# MPPT.net
KiCad netlist of a schematic drawn in Altium Designer
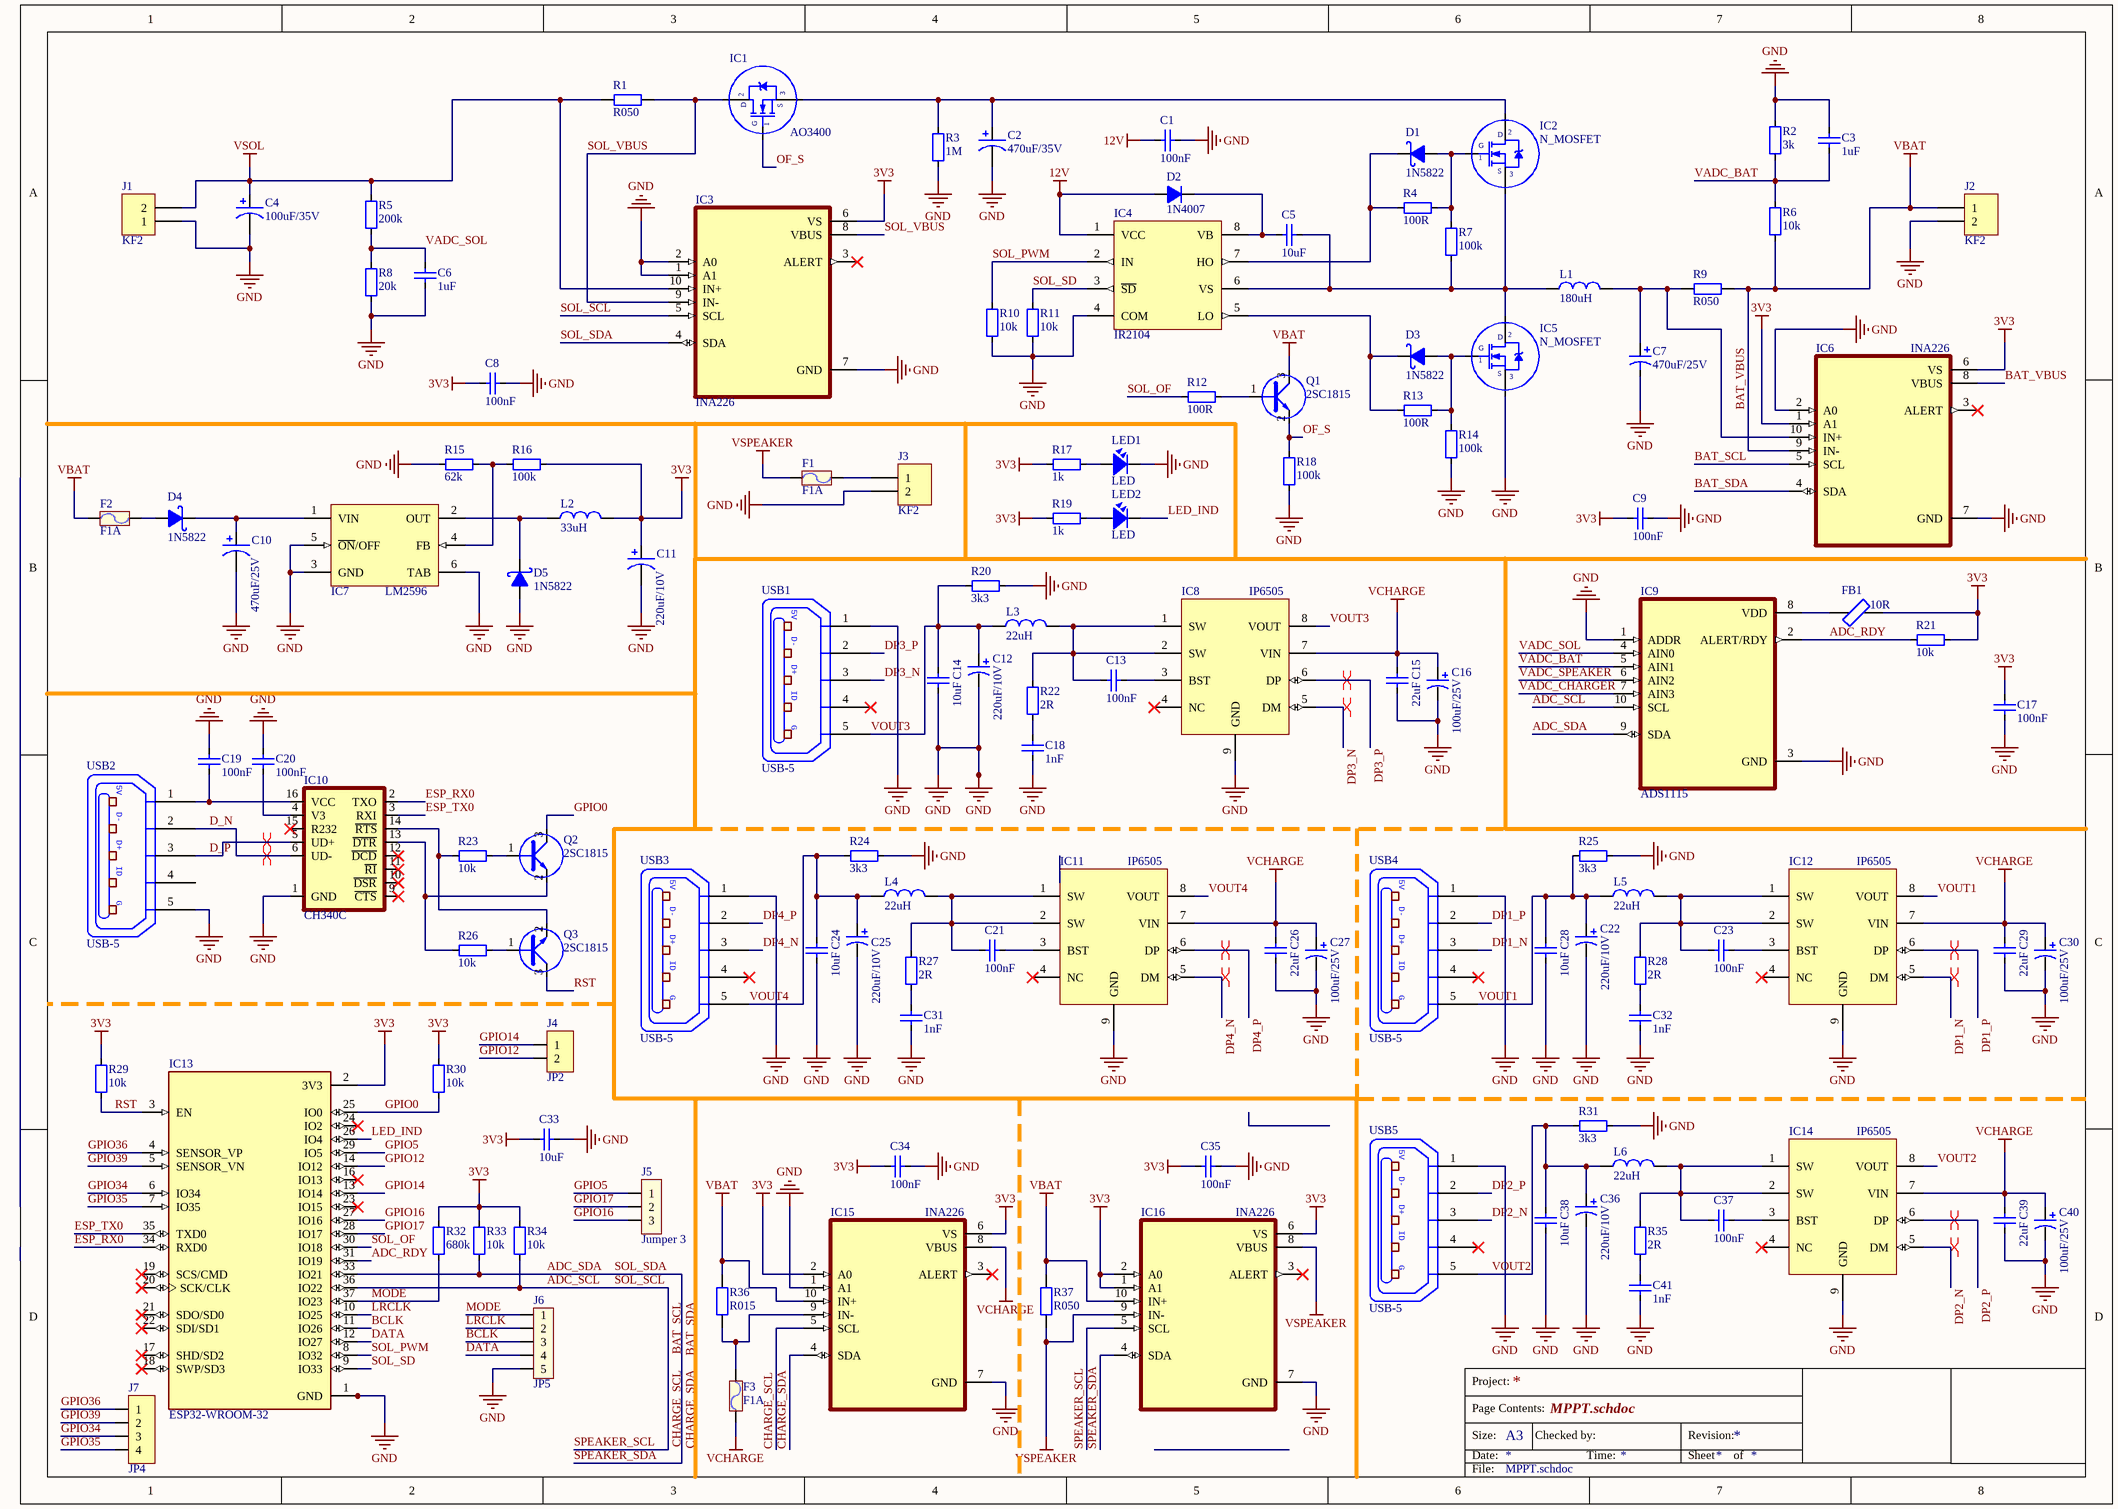
[diagram p0: MPPT.schdoc]

(export (version "E")
  (design (tool "Eeschema 10.0.6"))
  (components
    (comp (ref "C1")
      (value "100nF")
      (footprint "CAP_0805")
      (description "Capacitor")
      (fields (field (name "PUBLISHER") "Altium Limited"))
      (libsource (lib "My Library") (part "CapSMD"))
    )
    (comp (ref "C2")
      (value "470uF/35V")
      (footprint "CAP_H17_D10")
      (description "Polarized Capacitor (Axial)")
      (fields (field (name "PUBLISHER") "Altium Limited"))
      (libsource (lib "My Library") (part "Cap Pol"))
    )
    (comp (ref "C3")
      (value "1uF")
      (footprint "CAP_0805")
      (description "Capacitor")
      (fields (field (name "PUBLISHER") "Altium Limited"))
      (libsource (lib "My Library") (part "CapSMD"))
    )
    (comp (ref "C4")
      (value "100uF/35V")
      (footprint "CAP_H12_D06")
      (description "Polarized Capacitor (Axial)")
      (fields (field (name "PUBLISHER") "Altium Limited"))
      (libsource (lib "My Library") (part "Cap Pol"))
    )
    (comp (ref "C5")
      (value "10uF")
      (footprint "CAP_0805")
      (description "Capacitor")
      (fields (field (name "PUBLISHER") "Altium Limited"))
      (libsource (lib "My Library") (part "CapSMD"))
    )
    (comp (ref "C6")
      (value "1uF")
      (footprint "CAP_0805")
      (description "Capacitor")
      (fields (field (name "PUBLISHER") "Altium Limited"))
      (libsource (lib "My Library") (part "CapSMD"))
    )
    (comp (ref "C7")
      (value "470uF/25V")
      (footprint "C8mm")
      (description "Polarized Capacitor (Axial)")
      (fields (field (name "PUBLISHER") "Altium Limited"))
      (libsource (lib "") (part "Cap Pol_1"))
    )
    (comp (ref "C8")
      (value "100nF")
      (footprint "CAP_0805")
      (description "Capacitor")
      (fields (field (name "PUBLISHER") "Altium Limited"))
      (libsource (lib "My Library") (part "CapSMD"))
    )
    (comp (ref "C9")
      (value "100nF")
      (footprint "CAP_0805")
      (description "Capacitor")
      (fields (field (name "PUBLISHER") "Altium Limited"))
      (libsource (lib "My Library") (part "CapSMD"))
    )
    (comp (ref "C10")
      (value "470uF/25V")
      (footprint "C8mm")
      (description "Polarized Capacitor (Axial)")
      (fields (field (name "PUBLISHER") "Altium Limited"))
      (libsource (lib "My Library") (part "Cap Pol"))
    )
    (comp (ref "C11")
      (value "220uF/10V")
      (footprint "C5mm")
      (description "Polarized Capacitor (Axial)")
      (fields (field (name "PUBLISHER") "Altium Limited"))
      (libsource (lib "My Library") (part "Cap Pol"))
    )
    (comp (ref "C12")
      (value "220uF/10V")
      (footprint "CAP_3216")
      (description "Polazied Tantalum Capacitor")
      (libsource (lib "My Library") (part "CAP_TAN_SMD"))
    )
    (comp (ref "C13")
      (value "100nF")
      (footprint "CAP_0805")
      (description "Capacitor")
      (fields (field (name "PUBLISHER") "Altium Limited"))
      (libsource (lib "My Library") (part "CapSMD"))
    )
    (comp (ref "C14")
      (value "10uF")
      (footprint "CAP_0805")
      (description "Capacitor")
      (fields (field (name "PUBLISHER") "Altium Limited"))
      (libsource (lib "My Library") (part "CapSMD"))
    )
    (comp (ref "C15")
      (value "22uF")
      (footprint "CAP_0805")
      (description "Capacitor")
      (fields (field (name "PUBLISHER") "Altium Limited"))
      (libsource (lib "My Library") (part "CapSMD"))
    )
    (comp (ref "C16")
      (value "100uF/25V")
      (footprint "CAP_3528")
      (description "Polazied Tantalum Capacitor")
      (libsource (lib "My Library") (part "CAP_TAN_SMD"))
    )
    (comp (ref "C17")
      (value "100nF")
      (footprint "CAP_0805")
      (description "Capacitor")
      (fields (field (name "PUBLISHER") "Altium Limited"))
      (libsource (lib "My Library") (part "CapSMD"))
    )
    (comp (ref "C18")
      (value "1nF")
      (footprint "CAP_0805")
      (description "Capacitor")
      (fields (field (name "PUBLISHER") "Altium Limited"))
      (libsource (lib "My Library") (part "CapSMD"))
    )
    (comp (ref "C19")
      (value "100nF")
      (footprint "CAP_0805")
      (description "Capacitor")
      (fields (field (name "PUBLISHER") "Altium Limited"))
      (libsource (lib "My Library") (part "CapSMD"))
    )
    (comp (ref "C20")
      (value "100nF")
      (footprint "CAP_0805")
      (description "Capacitor")
      (fields (field (name "PUBLISHER") "Altium Limited"))
      (libsource (lib "My Library") (part "CapSMD"))
    )
    (comp (ref "C21")
      (value "100nF")
      (footprint "CAP_0805")
      (description "Capacitor")
      (fields (field (name "PUBLISHER") "Altium Limited"))
      (libsource (lib "My Library") (part "CapSMD"))
    )
    (comp (ref "C22")
      (value "220uF/10V")
      (footprint "CAP_3216")
      (description "Polazied Tantalum Capacitor")
      (libsource (lib "My Library") (part "CAP_TAN_SMD"))
    )
    (comp (ref "C23")
      (value "100nF")
      (footprint "CAP_0805")
      (description "Capacitor")
      (fields (field (name "PUBLISHER") "Altium Limited"))
      (libsource (lib "My Library") (part "CapSMD"))
    )
    (comp (ref "C24")
      (value "10uF")
      (footprint "CAP_0805")
      (description "Capacitor")
      (fields (field (name "PUBLISHER") "Altium Limited"))
      (libsource (lib "My Library") (part "CapSMD"))
    )
    (comp (ref "C25")
      (value "220uF/10V")
      (footprint "CAP_3216")
      (description "Polazied Tantalum Capacitor")
      (libsource (lib "My Library") (part "CAP_TAN_SMD"))
    )
    (comp (ref "C26")
      (value "22uF")
      (footprint "CAP_0805")
      (description "Capacitor")
      (fields (field (name "PUBLISHER") "Altium Limited"))
      (libsource (lib "My Library") (part "CapSMD"))
    )
    (comp (ref "C27")
      (value "100uF/25V")
      (footprint "CAP_3528")
      (description "Polazied Tantalum Capacitor")
      (libsource (lib "My Library") (part "CAP_TAN_SMD"))
    )
    (comp (ref "C28")
      (value "10uF")
      (footprint "CAP_0805")
      (description "Capacitor")
      (fields (field (name "PUBLISHER") "Altium Limited"))
      (libsource (lib "My Library") (part "CapSMD"))
    )
    (comp (ref "C29")
      (value "22uF")
      (footprint "CAP_0805")
      (description "Capacitor")
      (fields (field (name "PUBLISHER") "Altium Limited"))
      (libsource (lib "My Library") (part "CapSMD"))
    )
    (comp (ref "C30")
      (value "100uF/25V")
      (footprint "CAP_3528")
      (description "Polazied Tantalum Capacitor")
      (libsource (lib "My Library") (part "CAP_TAN_SMD"))
    )
    (comp (ref "C31")
      (value "1nF")
      (footprint "CAP_0805")
      (description "Capacitor")
      (fields (field (name "PUBLISHER") "Altium Limited"))
      (libsource (lib "My Library") (part "CapSMD"))
    )
    (comp (ref "C32")
      (value "1nF")
      (footprint "CAP_0805")
      (description "Capacitor")
      (fields (field (name "PUBLISHER") "Altium Limited"))
      (libsource (lib "My Library") (part "CapSMD"))
    )
    (comp (ref "C33")
      (value "10uF")
      (footprint "CAP_0805")
      (description "Capacitor")
      (fields (field (name "PUBLISHER") "Altium Limited"))
      (libsource (lib "My Library") (part "CapSMD"))
    )
    (comp (ref "C34")
      (value "100nF")
      (footprint "CAP_0805")
      (description "Capacitor")
      (fields (field (name "PUBLISHER") "Altium Limited"))
      (libsource (lib "My Library") (part "CapSMD"))
    )
    (comp (ref "C35")
      (value "100nF")
      (footprint "CAP_0805")
      (description "Capacitor")
      (fields (field (name "PUBLISHER") "Altium Limited"))
      (libsource (lib "My Library") (part "CapSMD"))
    )
    (comp (ref "C36")
      (value "220uF/10V")
      (footprint "CAP_3216")
      (description "Polazied Tantalum Capacitor")
      (libsource (lib "My Library") (part "CAP_TAN_SMD"))
    )
    (comp (ref "C37")
      (value "100nF")
      (footprint "CAP_0805")
      (description "Capacitor")
      (fields (field (name "PUBLISHER") "Altium Limited"))
      (libsource (lib "My Library") (part "CapSMD"))
    )
    (comp (ref "C38")
      (value "10uF")
      (footprint "CAP_0805")
      (description "Capacitor")
      (fields (field (name "PUBLISHER") "Altium Limited"))
      (libsource (lib "My Library") (part "CapSMD"))
    )
    (comp (ref "C39")
      (value "22uF")
      (footprint "CAP_0805")
      (description "Capacitor")
      (fields (field (name "PUBLISHER") "Altium Limited"))
      (libsource (lib "My Library") (part "CapSMD"))
    )
    (comp (ref "C40")
      (value "100uF/25V")
      (footprint "CAP_3528")
      (description "Polazied Tantalum Capacitor")
      (libsource (lib "My Library") (part "CAP_TAN_SMD"))
    )
    (comp (ref "C41")
      (value "1nF")
      (footprint "CAP_0805")
      (description "Capacitor")
      (fields (field (name "PUBLISHER") "Altium Limited"))
      (libsource (lib "My Library") (part "CapSMD"))
    )
    (comp (ref "D1")
      (value "1N5822")
      (footprint "DIO-214AC(SMA)")
      (description "Schottky Rectifiers")
      (libsource (lib "My Library") (part "1N5822"))
    )
    (comp (ref "D2")
      (value "1N4007")
      (footprint "D1A")
      (description "Diode 1A")
      (libsource (lib "My Library") (part "D1A"))
    )
    (comp (ref "D3")
      (value "1N5822")
      (footprint "DIO-214AC(SMA)")
      (description "Schottky Rectifiers")
      (libsource (lib "My Library") (part "1N5822"))
    )
    (comp (ref "D4")
      (value "1N5822")
      (footprint "DIO-214AC(SMA)")
      (description "Schottky Rectifiers")
      (libsource (lib "My Library") (part "1N5822"))
    )
    (comp (ref "D5")
      (value "1N5822")
      (footprint "DIO-214AC(SMA)")
      (description "Schottky Rectifiers")
      (libsource (lib "My Library") (part "1N5822"))
    )
    (comp (ref "F1")
      (value "F1A")
      (footprint "FUSE2")
      (description "Fuse")
      (fields (field (name "DESIGNED BY") "VanDungEvn"))
      (libsource (lib "My Library") (part "Fuse"))
    )
    (comp (ref "F2")
      (value "F1A")
      (footprint "RES-SMD-1206")
      (description "Fuse")
      (fields (field (name "DESIGNED BY") "VanDungEvn"))
      (libsource (lib "My Library") (part "Fuse"))
    )
    (comp (ref "F3")
      (value "F1A")
      (footprint "RES-1WD")
      (description "Fuse")
      (fields (field (name "DESIGNED BY") "VanDungEvn"))
      (libsource (lib "") (part "Fuse_1"))
    )
    (comp (ref "FB1")
      (value "10R")
      (footprint "RES-SMD-0805")
      (description "Generic Ferrit Bead")
      (libsource (lib "My Library") (part "Ferrit Bead"))
    )
    (comp (ref "IC1")
      (value "AO3400")
      (footprint "SOT23A")
      (description "Generic N Channel MOSFET")
      (libsource (lib "My Library") (part "MOSFET_N"))
    )
    (comp (ref "IC2")
      (value "N_MOSFET")
      (footprint "TO-220")
      (description "Generic N Channel MOSFET")
      (libsource (lib "My Library") (part "MOSFET_N"))
    )
    (comp (ref "IC3")
      (value "INA226")
      (footprint "VSSOP-10")
      (description "Current Sensing IC")
      (libsource (lib "My Library") (part "INA226"))
    )
    (comp (ref "IC4")
      (value "IR2104")
      (footprint "SOP-8")
      (description "PWM Driver")
      (libsource (lib "My Library") (part "IR2104"))
    )
    (comp (ref "IC5")
      (value "N_MOSFET")
      (footprint "TO-220")
      (description "Generic N Channel MOSFET")
      (libsource (lib "My Library") (part "MOSFET_N"))
    )
    (comp (ref "IC6")
      (value "INA226")
      (footprint "VSSOP-10")
      (description "Current Sensing IC")
      (libsource (lib "My Library") (part "INA226"))
    )
    (comp (ref "IC7") (value "LM2596") (footprint "TO263-5") (libsource (lib "My Library") (part "LM2576")))
    (comp (ref "IC8")
      (value "IP6505")
      (footprint "ESOP-8")
      (description "DC/DC Converter Charge IC QC/DCP/...")
      (libsource (lib "My Library") (part "IP6505"))
    )
    (comp (ref "IC9")
      (value "ADS1115")
      (footprint "SOP50P490X110-10N")
      (description "16 bits 4 channals ADC IC")
      (libsource (lib "My Library") (part "ADS1115"))
    )
    (comp (ref "IC10")
      (value "CH340C")
      (footprint "SO016")
      (description "USB to serial chip CH340")
      (fields (field (name "MF") "WCH"))
      (libsource (lib "My Library") (part "CH340C"))
    )
    (comp (ref "IC11")
      (value "IP6505")
      (footprint "ESOP-8")
      (description "DC/DC Converter Charge IC QC/DCP/...")
      (libsource (lib "My Library") (part "IP6505"))
    )
    (comp (ref "IC12")
      (value "IP6505")
      (footprint "ESOP-8")
      (description "DC/DC Converter Charge IC QC/DCP/...")
      (libsource (lib "My Library") (part "IP6505"))
    )
    (comp (ref "IC13")
      (value "ESP32-WROOM-32")
      (footprint "MODULE_ESP32-WROOM-32")
      (description "Bluetooth, WiFi Transceiver Module 2.4GHz ~ 2.5GHz Surface Mount")
      (fields (field (name "MF") "Espressif Systems") (field (name "DIGI-KEY_PART_NUMBER") "1904-1010-1-ND"))
      (libsource (lib "My Library") (part "ESP32-WROOM-32"))
    )
    (comp (ref "IC14")
      (value "IP6505")
      (footprint "ESOP-8")
      (description "DC/DC Converter Charge IC QC/DCP/...")
      (libsource (lib "My Library") (part "IP6505"))
    )
    (comp (ref "IC15")
      (value "INA226")
      (footprint "VSSOP-10")
      (description "Current Sensing IC")
      (libsource (lib "My Library") (part "INA226"))
    )
    (comp (ref "IC16")
      (value "INA226")
      (footprint "VSSOP-10")
      (description "Current Sensing IC")
      (libsource (lib "My Library") (part "INA226"))
    )
    (comp (ref "J1")
      (value "KF2")
      (footprint "KF2-5.08")
      (fields
        (field (name "MANUFACTURER") "Würth Elektronik eiSos GmbH")
        (field (name "PARTNO") "691103110002")
        (field (name "CREATED BY") "Karrer Zheng")
      )
      (libsource (lib "") (part "KF2_1"))
    )
    (comp (ref "J2")
      (value "KF2")
      (footprint "KF2-5.08")
      (fields
        (field (name "MANUFACTURER") "Würth Elektronik eiSos GmbH")
        (field (name "PARTNO") "691103110002")
        (field (name "CREATED BY") "Karrer Zheng")
      )
      (libsource (lib "My Library") (part "KF2"))
    )
    (comp (ref "J3")
      (value "KF2")
      (footprint "KF2-5.08")
      (fields
        (field (name "MANUFACTURER") "Würth Elektronik eiSos GmbH")
        (field (name "PARTNO") "691103110002")
        (field (name "CREATED BY") "Karrer Zheng")
      )
      (libsource (lib "My Library") (part "KF2"))
    )
    (comp (ref "J4")
      (value "JP2")
      (footprint "JP2-C1T")
      (description "WR-PHD 2.54 mm Angled Socket Header")
      (fields
        (field (name "MANUFACTURER") "Würth Elektronik eiSos GmbH")
        (field (name "PARTNO") "613002143121")
        (field (name "CREATED BY") "Karrer Zheng")
      )
      (libsource (lib "My Library") (part "JP2"))
    )
    (comp (ref "J5") (value "Jumper 3") (footprint "JP3-C1T") (libsource (lib "My Library") (part "JP3")))
    (comp (ref "J6") (value "JP5") (footprint "JP5") (libsource (lib "My Library") (part "JP5")))
    (comp (ref "J7")
      (value "JP4")
      (footprint "JP4-C1T")
      (description "WR-PHD 2.54 mm Angled Socket Header")
      (fields
        (field (name "MANUFACTURER") "Würth Elektronik eiSos GmbH")
        (field (name "PARTNO") "613004143121")
        (field (name "CREATED BY") "Karrer Zheng")
      )
      (libsource (lib "My Library") (part "JP4"))
    )
    (comp (ref "L1")
      (value "180uH")
      (footprint "L-DIP-M-13.5x6")
      (description "180uH 4A 13mm")
      (libsource (lib "My Library") (part "Inductor"))
    )
    (comp (ref "L2")
      (value "33uH")
      (footprint "L-DIP-M-13.5x6")
      (description "180uH 4A 13mm")
      (libsource (lib "My Library") (part "Inductor"))
    )
    (comp (ref "L3")
      (value "22uH")
      (footprint "L-SMD-M-12x10")
      (description "180uH 4A 13mm")
      (libsource (lib "My Library") (part "Inductor"))
    )
    (comp (ref "L4")
      (value "22uH")
      (footprint "L-SMD-M-12x10")
      (description "180uH 4A 13mm")
      (libsource (lib "My Library") (part "Inductor"))
    )
    (comp (ref "L5")
      (value "22uH")
      (footprint "L-SMD-M-12x10")
      (description "180uH 4A 13mm")
      (libsource (lib "My Library") (part "Inductor"))
    )
    (comp (ref "L6")
      (value "22uH")
      (footprint "L-SMD-M-12x10")
      (description "180uH 4A 13mm")
      (libsource (lib "My Library") (part "Inductor"))
    )
    (comp (ref "LED1")
      (value "LED")
      (footprint "LED-0805-Red")
      (description "LED Single colour Green and Red")
      (libsource (lib "My Library") (part "LED"))
    )
    (comp (ref "LED2")
      (value "LED")
      (footprint "LED-0805-Red")
      (description "LED Single colour Green and Red")
      (libsource (lib "My Library") (part "LED"))
    )
    (comp (ref "Q1")
      (value "2SC1815")
      (footprint "SOT23D")
      (description "NPN 600mW, ECB")
      (libsource (lib "") (part "C1815_1"))
    )
    (comp (ref "Q2")
      (value "2SC1815")
      (footprint "SOT23D")
      (description "NPN 600mW, ECB")
      (libsource (lib "") (part "C1815_1"))
    )
    (comp (ref "Q3")
      (value "2SC1815")
      (footprint "SOT23D")
      (description "NPN 600mW, ECB")
      (libsource (lib "My Library") (part "C1815"))
    )
    (comp (ref "R1")
      (value "R050")
      (footprint "RES-SMD-2512")
      (description "Resistor SMD")
      (fields
        (field (name "MANUFACTURER") "Generic Components")
        (field (name "PUBLISHER") "Altium Hobart Technology Centre")
      )
      (libsource (lib "") (part "Resistor - SMD_1"))
    )
    (comp (ref "R2")
      (value "3k")
      (footprint "RES-SMD-0805")
      (description "Resistor")
      (fields
        (field (name "MANUFACTURER") "Generic Components")
        (field (name "PUBLISHER") "Altium Hobart Technology Centre")
      )
      (libsource (lib "My Library") (part "Resistor - SMD"))
    )
    (comp (ref "R3")
      (value "1M")
      (footprint "RES-SMD-0805")
      (description "Resistor")
      (fields
        (field (name "MANUFACTURER") "Generic Components")
        (field (name "PUBLISHER") "Altium Hobart Technology Centre")
      )
      (libsource (lib "My Library") (part "Resistor - SMD"))
    )
    (comp (ref "R4")
      (value "100R")
      (footprint "RES-SMD-0805")
      (description "Resistor")
      (fields
        (field (name "MANUFACTURER") "Generic Components")
        (field (name "PUBLISHER") "Altium Hobart Technology Centre")
      )
      (libsource (lib "My Library") (part "Resistor - SMD"))
    )
    (comp (ref "R5")
      (value "200k")
      (footprint "RES-SMD-0805")
      (description "Resistor")
      (fields
        (field (name "MANUFACTURER") "Generic Components")
        (field (name "PUBLISHER") "Altium Hobart Technology Centre")
      )
      (libsource (lib "My Library") (part "Resistor - SMD"))
    )
    (comp (ref "R6")
      (value "10k")
      (footprint "RES-SMD-0805")
      (description "Resistor")
      (fields
        (field (name "MANUFACTURER") "Generic Components")
        (field (name "PUBLISHER") "Altium Hobart Technology Centre")
      )
      (libsource (lib "My Library") (part "Resistor - SMD"))
    )
    (comp (ref "R7")
      (value "100k")
      (footprint "RES-SMD-0805")
      (description "Resistor")
      (fields
        (field (name "MANUFACTURER") "Generic Components")
        (field (name "PUBLISHER") "Altium Hobart Technology Centre")
      )
      (libsource (lib "My Library") (part "Resistor - SMD"))
    )
    (comp (ref "R8")
      (value "20k")
      (footprint "RES-SMD-0805")
      (description "Resistor")
      (fields
        (field (name "MANUFACTURER") "Generic Components")
        (field (name "PUBLISHER") "Altium Hobart Technology Centre")
      )
      (libsource (lib "My Library") (part "Resistor - SMD"))
    )
    (comp (ref "R9")
      (value "R050")
      (footprint "RES-SMD-2512")
      (description "Resistor SMD")
      (fields
        (field (name "MANUFACTURER") "Generic Components")
        (field (name "PUBLISHER") "Altium Hobart Technology Centre")
      )
      (libsource (lib "") (part "Resistor - SMD_1"))
    )
    (comp (ref "R10")
      (value "10k")
      (footprint "RES-SMD-0805")
      (description "Resistor")
      (fields
        (field (name "MANUFACTURER") "Generic Components")
        (field (name "PUBLISHER") "Altium Hobart Technology Centre")
      )
      (libsource (lib "My Library") (part "Resistor - SMD"))
    )
    (comp (ref "R11")
      (value "10k")
      (footprint "RES-SMD-0805")
      (description "Resistor")
      (fields
        (field (name "MANUFACTURER") "Generic Components")
        (field (name "PUBLISHER") "Altium Hobart Technology Centre")
      )
      (libsource (lib "My Library") (part "Resistor - SMD"))
    )
    (comp (ref "R12")
      (value "100R")
      (footprint "RES-SMD-0805")
      (description "Resistor")
      (fields
        (field (name "MANUFACTURER") "Generic Components")
        (field (name "PUBLISHER") "Altium Hobart Technology Centre")
      )
      (libsource (lib "My Library") (part "Resistor - SMD"))
    )
    (comp (ref "R13")
      (value "100R")
      (footprint "RES-SMD-0805")
      (description "Resistor")
      (fields
        (field (name "MANUFACTURER") "Generic Components")
        (field (name "PUBLISHER") "Altium Hobart Technology Centre")
      )
      (libsource (lib "My Library") (part "Resistor - SMD"))
    )
    (comp (ref "R14")
      (value "100k")
      (footprint "RES-SMD-0805")
      (description "Resistor")
      (fields
        (field (name "MANUFACTURER") "Generic Components")
        (field (name "PUBLISHER") "Altium Hobart Technology Centre")
      )
      (libsource (lib "My Library") (part "Resistor - SMD"))
    )
    (comp (ref "R15")
      (value "62k")
      (footprint "RES-SMD-0805")
      (description "Resistor")
      (fields
        (field (name "MANUFACTURER") "Generic Components")
        (field (name "PUBLISHER") "Altium Hobart Technology Centre")
      )
      (libsource (lib "My Library") (part "Resistor - SMD"))
    )
    (comp (ref "R16")
      (value "100k")
      (footprint "RES-SMD-0805")
      (description "Resistor")
      (fields
        (field (name "MANUFACTURER") "Generic Components")
        (field (name "PUBLISHER") "Altium Hobart Technology Centre")
      )
      (libsource (lib "My Library") (part "Resistor - SMD"))
    )
    (comp (ref "R17")
      (value "1k")
      (footprint "RES-SMD-0805")
      (description "Resistor")
      (fields
        (field (name "MANUFACTURER") "Generic Components")
        (field (name "PUBLISHER") "Altium Hobart Technology Centre")
      )
      (libsource (lib "My Library") (part "Resistor - SMD"))
    )
    (comp (ref "R18")
      (value "100k")
      (footprint "RES-SMD-0805")
      (description "Resistor")
      (fields
        (field (name "MANUFACTURER") "Generic Components")
        (field (name "PUBLISHER") "Altium Hobart Technology Centre")
      )
      (libsource (lib "My Library") (part "Resistor - SMD"))
    )
    (comp (ref "R19")
      (value "1k")
      (footprint "RES-SMD-0805")
      (description "Resistor")
      (fields
        (field (name "MANUFACTURER") "Generic Components")
        (field (name "PUBLISHER") "Altium Hobart Technology Centre")
      )
      (libsource (lib "My Library") (part "Resistor - SMD"))
    )
    (comp (ref "R20")
      (value "3k3")
      (footprint "RES-SMD-0805")
      (description "Resistor")
      (fields
        (field (name "MANUFACTURER") "Generic Components")
        (field (name "PUBLISHER") "Altium Hobart Technology Centre")
      )
      (libsource (lib "My Library") (part "Resistor - SMD"))
    )
    (comp (ref "R21")
      (value "10k")
      (footprint "RES-SMD-0805")
      (description "Resistor")
      (fields
        (field (name "MANUFACTURER") "Generic Components")
        (field (name "PUBLISHER") "Altium Hobart Technology Centre")
      )
      (libsource (lib "My Library") (part "Resistor - SMD"))
    )
    (comp (ref "R22")
      (value "2R")
      (footprint "RES-SMD-0805")
      (description "Resistor")
      (fields
        (field (name "MANUFACTURER") "Generic Components")
        (field (name "PUBLISHER") "Altium Hobart Technology Centre")
      )
      (libsource (lib "My Library") (part "Resistor - SMD"))
    )
    (comp (ref "R23")
      (value "10k")
      (footprint "RES-SMD-0805")
      (description "Resistor")
      (fields
        (field (name "MANUFACTURER") "Generic Components")
        (field (name "PUBLISHER") "Altium Hobart Technology Centre")
      )
      (libsource (lib "My Library") (part "Resistor - SMD"))
    )
    (comp (ref "R24")
      (value "3k3")
      (footprint "RES-SMD-0805")
      (description "Resistor")
      (fields
        (field (name "MANUFACTURER") "Generic Components")
        (field (name "PUBLISHER") "Altium Hobart Technology Centre")
      )
      (libsource (lib "My Library") (part "Resistor - SMD"))
    )
    (comp (ref "R25")
      (value "3k3")
      (footprint "RES-SMD-0805")
      (description "Resistor")
      (fields
        (field (name "MANUFACTURER") "Generic Components")
        (field (name "PUBLISHER") "Altium Hobart Technology Centre")
      )
      (libsource (lib "My Library") (part "Resistor - SMD"))
    )
    (comp (ref "R26")
      (value "10k")
      (footprint "RES-SMD-0805")
      (description "Resistor")
      (fields
        (field (name "MANUFACTURER") "Generic Components")
        (field (name "PUBLISHER") "Altium Hobart Technology Centre")
      )
      (libsource (lib "My Library") (part "Resistor - SMD"))
    )
    (comp (ref "R27")
      (value "2R")
      (footprint "RES-SMD-0805")
      (description "Resistor")
      (fields
        (field (name "MANUFACTURER") "Generic Components")
        (field (name "PUBLISHER") "Altium Hobart Technology Centre")
      )
      (libsource (lib "My Library") (part "Resistor - SMD"))
    )
    (comp (ref "R28")
      (value "2R")
      (footprint "RES-SMD-0805")
      (description "Resistor")
      (fields
        (field (name "MANUFACTURER") "Generic Components")
        (field (name "PUBLISHER") "Altium Hobart Technology Centre")
      )
      (libsource (lib "My Library") (part "Resistor - SMD"))
    )
    (comp (ref "R29")
      (value "10k")
      (footprint "RES-SMD-0805")
      (description "Resistor")
      (fields
        (field (name "MANUFACTURER") "Generic Components")
        (field (name "PUBLISHER") "Altium Hobart Technology Centre")
      )
      (libsource (lib "My Library") (part "Resistor - SMD"))
    )
    (comp (ref "R30")
      (value "10k")
      (footprint "RES-SMD-0805")
      (description "Resistor")
      (fields
        (field (name "MANUFACTURER") "Generic Components")
        (field (name "PUBLISHER") "Altium Hobart Technology Centre")
      )
      (libsource (lib "My Library") (part "Resistor - SMD"))
    )
    (comp (ref "R31")
      (value "3k3")
      (footprint "RES-SMD-0805")
      (description "Resistor")
      (fields
        (field (name "MANUFACTURER") "Generic Components")
        (field (name "PUBLISHER") "Altium Hobart Technology Centre")
      )
      (libsource (lib "My Library") (part "Resistor - SMD"))
    )
    (comp (ref "R32")
      (value "680k")
      (footprint "RES-SMD-0805")
      (description "Resistor")
      (fields
        (field (name "MANUFACTURER") "Generic Components")
        (field (name "PUBLISHER") "Altium Hobart Technology Centre")
      )
      (libsource (lib "My Library") (part "Resistor - SMD"))
    )
    (comp (ref "R33")
      (value "10k")
      (footprint "RES-SMD-0805")
      (description "Resistor")
      (fields
        (field (name "MANUFACTURER") "Generic Components")
        (field (name "PUBLISHER") "Altium Hobart Technology Centre")
      )
      (libsource (lib "My Library") (part "Resistor - SMD"))
    )
    (comp (ref "R34")
      (value "10k")
      (footprint "RES-SMD-0805")
      (description "Resistor")
      (fields
        (field (name "MANUFACTURER") "Generic Components")
        (field (name "PUBLISHER") "Altium Hobart Technology Centre")
      )
      (libsource (lib "My Library") (part "Resistor - SMD"))
    )
    (comp (ref "R35")
      (value "2R")
      (footprint "RES-SMD-0805")
      (description "Resistor")
      (fields
        (field (name "MANUFACTURER") "Generic Components")
        (field (name "PUBLISHER") "Altium Hobart Technology Centre")
      )
      (libsource (lib "My Library") (part "Resistor - SMD"))
    )
    (comp (ref "R36")
      (value "R015")
      (footprint "RES-SMD-2512")
      (description "Resistor SMD")
      (fields
        (field (name "MANUFACTURER") "Generic Components")
        (field (name "PUBLISHER") "Altium Hobart Technology Centre")
      )
      (libsource (lib "") (part "Resistor - SMD_1"))
    )
    (comp (ref "R37")
      (value "R050")
      (footprint "RES-SMD-2512")
      (description "Resistor SMD")
      (fields
        (field (name "MANUFACTURER") "Generic Components")
        (field (name "PUBLISHER") "Altium Hobart Technology Centre")
      )
      (libsource (lib "") (part "Resistor - SMD_1"))
    )
    (comp (ref "USB1")
      (value "USB-5")
      (footprint "USB-D2")
      (fields
        (field (name "MANUFACTURER") "FCI")
        (field (name "MANUFACTURER PART NUMBER") "10118193-0001LF")
        (field (name ".CREATOR") "MM")
        (field (name ".CHECKED PCB") "RF")
        (field (name ".CHECKED SCH") "MM")
      )
      (libsource (lib "My Library") (part "USB-5"))
    )
    (comp (ref "USB2")
      (value "USB-5")
      (footprint "USB-M1")
      (fields
        (field (name "MANUFACTURER") "FCI")
        (field (name "MANUFACTURER PART NUMBER") "10118193-0001LF")
        (field (name ".CREATOR") "MM")
        (field (name ".CHECKED PCB") "RF")
        (field (name ".CHECKED SCH") "MM")
      )
      (libsource (lib "My Library") (part "USB-5"))
    )
    (comp (ref "USB3")
      (value "USB-5")
      (footprint "USB-D2")
      (fields
        (field (name "MANUFACTURER") "FCI")
        (field (name "MANUFACTURER PART NUMBER") "10118193-0001LF")
        (field (name ".CREATOR") "MM")
        (field (name ".CHECKED PCB") "RF")
        (field (name ".CHECKED SCH") "MM")
      )
      (libsource (lib "My Library") (part "USB-5"))
    )
    (comp (ref "USB4")
      (value "USB-5")
      (footprint "USB-D2")
      (fields
        (field (name "MANUFACTURER") "FCI")
        (field (name "MANUFACTURER PART NUMBER") "10118193-0001LF")
        (field (name ".CREATOR") "MM")
        (field (name ".CHECKED PCB") "RF")
        (field (name ".CHECKED SCH") "MM")
      )
      (libsource (lib "My Library") (part "USB-5"))
    )
    (comp (ref "USB5")
      (value "USB-5")
      (footprint "USB-D2")
      (fields
        (field (name "MANUFACTURER") "FCI")
        (field (name "MANUFACTURER PART NUMBER") "10118193-0001LF")
        (field (name ".CREATOR") "MM")
        (field (name ".CHECKED PCB") "RF")
        (field (name ".CHECKED SCH") "MM")
      )
      (libsource (lib "My Library") (part "USB-5"))
    )
  )
  (nets
    (net (code "1") (name "/ADC_RDY") (class "Default")
      (node (ref "IC13") (pin "31") (pinfunction "IO19_31") (pintype "bidirectional"))
      (node (ref "IC9") (pin "2") (pinfunction "ALERT/RDY_2") (pintype "output"))
      (node (ref "R21") (pin "2") (pinfunction "2_2") (pintype "passive"))
    )
    (net (code "2") (name "/ADC_SCL") (class "Default")
      (node (ref "IC13") (pin "36") (pinfunction "IO22_36") (pintype "bidirectional"))
      (node (ref "IC15") (pin "5") (pinfunction "SCL_5") (pintype "input"))
      (node (ref "IC16") (pin "5") (pinfunction "SCL_5") (pintype "input"))
      (node (ref "IC3") (pin "5") (pinfunction "SCL_5") (pintype "input"))
      (node (ref "IC6") (pin "5") (pinfunction "SCL_5") (pintype "input"))
      (node (ref "IC9") (pin "10") (pinfunction "SCL_10") (pintype "input"))
      (node (ref "R34") (pin "1") (pinfunction "1_1") (pintype "passive"))
    )
    (net (code "3") (name "/ADC_SDA") (class "Default")
      (node (ref "IC13") (pin "33") (pinfunction "IO21_33") (pintype "bidirectional"))
      (node (ref "IC15") (pin "4") (pinfunction "SDA_4") (pintype "bidirectional"))
      (node (ref "IC16") (pin "4") (pinfunction "SDA_4") (pintype "bidirectional"))
      (node (ref "IC3") (pin "4") (pinfunction "SDA_4") (pintype "bidirectional"))
      (node (ref "IC6") (pin "4") (pinfunction "SDA_4") (pintype "bidirectional"))
      (node (ref "IC9") (pin "9") (pinfunction "SDA_9") (pintype "bidirectional"))
      (node (ref "R33") (pin "1") (pinfunction "1_1") (pintype "passive"))
    )
    (net (code "4") (name "/BCLK") (class "Default")
      (node (ref "IC13") (pin "11") (pinfunction "IO26_11") (pintype "bidirectional"))
      (node (ref "J6") (pin "3") (pinfunction "3_3") (pintype "passive"))
    )
    (net (code "5") (name "/DATA") (class "Default")
      (node (ref "IC13") (pin "12") (pinfunction "IO27_12") (pintype "bidirectional"))
      (node (ref "J6") (pin "4") (pinfunction "4_4") (pintype "passive"))
    )
    (net (code "6") (name "/DP1_N") (class "Default")
      (node (ref "IC12") (pin "5") (pinfunction "DM_5") (pintype "bidirectional"))
      (node (ref "USB4") (pin "3") (pinfunction "P3_3") (pintype "passive"))
    )
    (net (code "7") (name "/DP1_P") (class "Default")
      (node (ref "IC12") (pin "6") (pinfunction "DP_6") (pintype "bidirectional"))
      (node (ref "USB4") (pin "2") (pinfunction "P2_2") (pintype "passive"))
    )
    (net (code "8") (name "/DP2_N") (class "Default")
      (node (ref "IC14") (pin "5") (pinfunction "DM_5") (pintype "bidirectional"))
      (node (ref "USB5") (pin "3") (pinfunction "P3_3") (pintype "passive"))
    )
    (net (code "9") (name "/DP2_P") (class "Default")
      (node (ref "IC14") (pin "6") (pinfunction "DP_6") (pintype "bidirectional"))
      (node (ref "USB5") (pin "2") (pinfunction "P2_2") (pintype "passive"))
    )
    (net (code "10") (name "/DP3_N") (class "Default")
      (node (ref "IC8") (pin "5") (pinfunction "DM_5") (pintype "bidirectional"))
      (node (ref "USB1") (pin "3") (pinfunction "P3_3") (pintype "passive"))
    )
    (net (code "11") (name "/DP3_P") (class "Default")
      (node (ref "IC8") (pin "6") (pinfunction "DP_6") (pintype "bidirectional"))
      (node (ref "USB1") (pin "2") (pinfunction "P2_2") (pintype "passive"))
    )
    (net (code "12") (name "/DP4_N") (class "Default")
      (node (ref "IC11") (pin "5") (pinfunction "DM_5") (pintype "bidirectional"))
      (node (ref "USB3") (pin "3") (pinfunction "P3_3") (pintype "passive"))
    )
    (net (code "13") (name "/DP4_P") (class "Default")
      (node (ref "IC11") (pin "6") (pinfunction "DP_6") (pintype "bidirectional"))
      (node (ref "USB3") (pin "2") (pinfunction "P2_2") (pintype "passive"))
    )
    (net (code "14") (name "/D_N") (class "Default")
      (node (ref "IC10") (pin "6") (pinfunction "UD-_6") (pintype "bidirectional"))
      (node (ref "USB2") (pin "2") (pinfunction "P2_2") (pintype "passive"))
    )
    (net (code "15") (name "/D_P") (class "Default")
      (node (ref "IC10") (pin "5") (pinfunction "UD+_5") (pintype "bidirectional"))
      (node (ref "USB2") (pin "3") (pinfunction "P3_3") (pintype "passive"))
    )
    (net (code "16") (name "/ESP_RX0") (class "Default")
      (node (ref "IC10") (pin "2") (pinfunction "TXO_2") (pintype "bidirectional"))
      (node (ref "IC13") (pin "34") (pinfunction "RXD0_34") (pintype "bidirectional"))
    )
    (net (code "17") (name "/ESP_TX0") (class "Default")
      (node (ref "IC10") (pin "3") (pinfunction "RXI_3") (pintype "bidirectional"))
      (node (ref "IC13") (pin "35") (pinfunction "TXD0_35") (pintype "bidirectional"))
    )
    (net (code "18") (name "/GPIO0") (class "Default")
      (node (ref "IC13") (pin "25") (pinfunction "IO0_25") (pintype "bidirectional"))
      (node (ref "Q2") (pin "3") (pinfunction "C_3") (pintype "passive"))
      (node (ref "R30") (pin "1") (pinfunction "1_1") (pintype "passive"))
    )
    (net (code "19") (name "/GPIO5") (class "Default")
      (node (ref "IC13") (pin "29") (pinfunction "IO5_29") (pintype "bidirectional"))
      (node (ref "J5") (pin "1") (pinfunction "1_1") (pintype "passive"))
    )
    (net (code "20") (name "/GPIO12") (class "Default")
      (node (ref "IC13") (pin "14") (pinfunction "IO12_14") (pintype "bidirectional"))
      (node (ref "J4") (pin "2") (pinfunction "2_2") (pintype "passive"))
    )
    (net (code "21") (name "/GPIO14") (class "Default")
      (node (ref "IC13") (pin "13") (pinfunction "IO14_13") (pintype "bidirectional"))
      (node (ref "J4") (pin "1") (pinfunction "1_1") (pintype "passive"))
    )
    (net (code "22") (name "/GPIO16") (class "Default")
      (node (ref "IC13") (pin "27") (pinfunction "IO16_27") (pintype "bidirectional"))
      (node (ref "J5") (pin "3") (pinfunction "3_3") (pintype "passive"))
    )
    (net (code "23") (name "/GPIO17") (class "Default")
      (node (ref "IC13") (pin "28") (pinfunction "IO17_28") (pintype "bidirectional"))
      (node (ref "J5") (pin "2") (pinfunction "2_2") (pintype "passive"))
    )
    (net (code "24") (name "/GPIO34") (class "Default")
      (node (ref "IC13") (pin "6") (pinfunction "IO34_6") (pintype "input"))
      (node (ref "J7") (pin "3") (pinfunction "3_3") (pintype "passive"))
    )
    (net (code "25") (name "/GPIO35") (class "Default")
      (node (ref "IC13") (pin "7") (pinfunction "IO35_7") (pintype "input"))
      (node (ref "J7") (pin "4") (pinfunction "4_4") (pintype "passive"))
    )
    (net (code "26") (name "/GPIO36") (class "Default")
      (node (ref "IC13") (pin "4") (pinfunction "SENSOR_VP_4") (pintype "input"))
      (node (ref "J7") (pin "1") (pinfunction "1_1") (pintype "passive"))
    )
    (net (code "27") (name "/GPIO39") (class "Default")
      (node (ref "IC13") (pin "5") (pinfunction "SENSOR_VN_5") (pintype "input"))
      (node (ref "J7") (pin "2") (pinfunction "2_2") (pintype "passive"))
    )
    (net (code "28") (name "/LED_IND") (class "Default")
      (node (ref "IC13") (pin "26") (pinfunction "IO4_26") (pintype "bidirectional"))
      (node (ref "LED2") (pin "2") (pinfunction "2_2") (pintype "passive"))
    )
    (net (code "29") (name "/LRCLK") (class "Default")
      (node (ref "IC13") (pin "10") (pinfunction "IO25_10") (pintype "bidirectional"))
      (node (ref "J6") (pin "2") (pinfunction "2_2") (pintype "passive"))
    )
    (net (code "30") (name "/MODE") (class "Default")
      (node (ref "IC13") (pin "37") (pinfunction "IO23_37") (pintype "bidirectional"))
      (node (ref "J6") (pin "1") (pinfunction "1_1") (pintype "passive"))
      (node (ref "R32") (pin "1") (pinfunction "1_1") (pintype "passive"))
    )
    (net (code "31") (name "/OF_S") (class "Default")
      (node (ref "IC1") (pin "1") (pinfunction "G_1") (pintype "passive"))
      (node (ref "Q1") (pin "2") (pinfunction "E_2") (pintype "passive"))
      (node (ref "R18") (pin "1") (pinfunction "1_1") (pintype "passive"))
    )
    (net (code "32") (name "/RST") (class "Default")
      (node (ref "IC13") (pin "3") (pinfunction "EN_3") (pintype "input"))
      (node (ref "Q3") (pin "3") (pinfunction "C_3") (pintype "passive"))
      (node (ref "R29") (pin "1") (pinfunction "1_1") (pintype "passive"))
    )
    (net (code "33") (name "/SOL_OF") (class "Default")
      (node (ref "IC13") (pin "30") (pinfunction "IO18_30") (pintype "bidirectional"))
      (node (ref "R12") (pin "2") (pinfunction "2_2") (pintype "passive"))
    )
    (net (code "34") (name "/SOL_PWM") (class "Default")
      (node (ref "IC13") (pin "8") (pinfunction "IO32_8") (pintype "bidirectional"))
      (node (ref "IC4") (pin "2") (pinfunction "IN_2") (pintype "output"))
      (node (ref "R10") (pin "2") (pinfunction "2_2") (pintype "passive"))
    )
    (net (code "35") (name "/SOL_SD") (class "Default")
      (node (ref "IC13") (pin "9") (pinfunction "IO33_9") (pintype "bidirectional"))
      (node (ref "IC4") (pin "3") (pinfunction "~{SD}_3") (pintype "output"))
      (node (ref "R11") (pin "2") (pinfunction "2_2") (pintype "passive"))
    )
    (net (code "36") (name "/SOL_VBUS") (class "Default")
      (node (ref "IC1") (pin "2") (pinfunction "D_2") (pintype "passive"))
      (node (ref "IC3") (pin "8") (pinfunction "VBUS_8") (pintype "power_in"))
      (node (ref "IC3") (pin "9") (pinfunction "IN-_9") (pintype "input"))
      (node (ref "R1") (pin "1") (pinfunction "1_1") (pintype "passive"))
    )
    (net (code "37") (name "/VADC_BAT") (class "Default")
      (node (ref "C3") (pin "2") (pinfunction "2_2") (pintype "passive"))
      (node (ref "IC9") (pin "5") (pinfunction "AIN1_5") (pintype "input"))
      (node (ref "R2") (pin "2") (pinfunction "2_2") (pintype "passive"))
      (node (ref "R6") (pin "1") (pinfunction "1_1") (pintype "passive"))
    )
    (net (code "38") (name "/VADC_CHARGER") (class "Default")
      (node (ref "IC9") (pin "7") (pinfunction "AIN3_7") (pintype "input"))
    )
    (net (code "39") (name "/VADC_SOL") (class "Default")
      (node (ref "C6") (pin "1") (pinfunction "1_1") (pintype "passive"))
      (node (ref "IC9") (pin "4") (pinfunction "AIN0_4") (pintype "input"))
      (node (ref "R5") (pin "1") (pinfunction "1_1") (pintype "passive"))
      (node (ref "R8") (pin "1") (pinfunction "1_1") (pintype "passive"))
    )
    (net (code "40") (name "/VADC_SPEAKER") (class "Default")
      (node (ref "IC9") (pin "6") (pinfunction "AIN2_6") (pintype "input"))
    )
    (net (code "41") (name "/VOUT1") (class "Default")
      (node (ref "C22") (pin "1") (pinfunction "1_1") (pintype "passive"))
      (node (ref "C28") (pin "1") (pinfunction "1_1") (pintype "passive"))
      (node (ref "IC12") (pin "8") (pinfunction "VOUT_8") (pintype "power_in"))
      (node (ref "L5") (pin "1") (pinfunction "1_1") (pintype "passive"))
      (node (ref "R25") (pin "1") (pinfunction "1_1") (pintype "passive"))
      (node (ref "USB4") (pin "5") (pinfunction "P5_5") (pintype "passive"))
    )
    (net (code "42") (name "/VOUT2") (class "Default")
      (node (ref "C36") (pin "1") (pinfunction "1_1") (pintype "passive"))
      (node (ref "C38") (pin "1") (pinfunction "1_1") (pintype "passive"))
      (node (ref "IC14") (pin "8") (pinfunction "VOUT_8") (pintype "power_in"))
      (node (ref "L6") (pin "1") (pinfunction "1_1") (pintype "passive"))
      (node (ref "R31") (pin "1") (pinfunction "1_1") (pintype "passive"))
      (node (ref "USB5") (pin "5") (pinfunction "P5_5") (pintype "passive"))
    )
    (net (code "43") (name "/VOUT3") (class "Default")
      (node (ref "C12") (pin "1") (pinfunction "1_1") (pintype "passive"))
      (node (ref "C14") (pin "1") (pinfunction "1_1") (pintype "passive"))
      (node (ref "IC8") (pin "8") (pinfunction "VOUT_8") (pintype "power_in"))
      (node (ref "L3") (pin "1") (pinfunction "1_1") (pintype "passive"))
      (node (ref "R20") (pin "1") (pinfunction "1_1") (pintype "passive"))
      (node (ref "USB1") (pin "5") (pinfunction "P5_5") (pintype "passive"))
    )
    (net (code "44") (name "/VOUT4") (class "Default")
      (node (ref "C24") (pin "1") (pinfunction "1_1") (pintype "passive"))
      (node (ref "C25") (pin "1") (pinfunction "1_1") (pintype "passive"))
      (node (ref "IC11") (pin "8") (pinfunction "VOUT_8") (pintype "power_in"))
      (node (ref "L4") (pin "1") (pinfunction "1_1") (pintype "passive"))
      (node (ref "R24") (pin "1") (pinfunction "1_1") (pintype "passive"))
      (node (ref "USB3") (pin "5") (pinfunction "P5_5") (pintype "passive"))
    )
    (net (code "45") (name "3V3") (class "Default")
      (node (ref "C11") (pin "1") (pinfunction "1_1") (pintype "passive"))
      (node (ref "C17") (pin "1") (pinfunction "1_1") (pintype "passive"))
      (node (ref "C33") (pin "1") (pinfunction "1_1") (pintype "passive"))
      (node (ref "C34") (pin "1") (pinfunction "1_1") (pintype "passive"))
      (node (ref "C35") (pin "1") (pinfunction "1_1") (pintype "passive"))
      (node (ref "C8") (pin "1") (pinfunction "1_1") (pintype "passive"))
      (node (ref "C9") (pin "1") (pinfunction "1_1") (pintype "passive"))
      (node (ref "FB1") (pin "2") (pintype "passive"))
      (node (ref "IC13") (pin "2") (pinfunction "3V3_2") (pintype "power_in"))
      (node (ref "IC15") (pin "2") (pinfunction "A0_2") (pintype "input"))
      (node (ref "IC15") (pin "6") (pinfunction "VS_6") (pintype "power_in"))
      (node (ref "IC16") (pin "1") (pinfunction "A1_1") (pintype "input"))
      (node (ref "IC16") (pin "2") (pinfunction "A0_2") (pintype "input"))
      (node (ref "IC16") (pin "6") (pinfunction "VS_6") (pintype "power_in"))
      (node (ref "IC3") (pin "6") (pinfunction "VS_6") (pintype "power_in"))
      (node (ref "IC6") (pin "1") (pinfunction "A1_1") (pintype "input"))
      (node (ref "IC6") (pin "6") (pinfunction "VS_6") (pintype "power_in"))
      (node (ref "L2") (pin "2") (pinfunction "2_2") (pintype "passive"))
      (node (ref "R16") (pin "2") (pinfunction "2_2") (pintype "passive"))
      (node (ref "R17") (pin "2") (pinfunction "2_2") (pintype "passive"))
      (node (ref "R19") (pin "2") (pinfunction "2_2") (pintype "passive"))
      (node (ref "R21") (pin "1") (pinfunction "1_1") (pintype "passive"))
      (node (ref "R29") (pin "2") (pinfunction "2_2") (pintype "passive"))
      (node (ref "R30") (pin "2") (pinfunction "2_2") (pintype "passive"))
      (node (ref "R32") (pin "2") (pinfunction "2_2") (pintype "passive"))
      (node (ref "R33") (pin "2") (pinfunction "2_2") (pintype "passive"))
      (node (ref "R34") (pin "2") (pinfunction "2_2") (pintype "passive"))
    )
    (net (code "46") (name "12V") (class "Default")
      (node (ref "C1") (pin "1") (pinfunction "1_1") (pintype "passive"))
      (node (ref "D2") (pin "1") (pinfunction "A_1") (pintype "passive"))
      (node (ref "IC4") (pin "1") (pinfunction "VCC_1") (pintype "power_in"))
    )
    (net (code "47") (name "GND") (class "Default")
      (node (ref "C1") (pin "2") (pinfunction "2_2") (pintype "passive"))
      (node (ref "C10") (pin "2") (pinfunction "2_2") (pintype "passive"))
      (node (ref "C11") (pin "2") (pinfunction "2_2") (pintype "passive"))
      (node (ref "C12") (pin "2") (pinfunction "2_2") (pintype "passive"))
      (node (ref "C14") (pin "2") (pinfunction "2_2") (pintype "passive"))
      (node (ref "C15") (pin "2") (pinfunction "2_2") (pintype "passive"))
      (node (ref "C16") (pin "2") (pinfunction "2_2") (pintype "passive"))
      (node (ref "C17") (pin "2") (pinfunction "2_2") (pintype "passive"))
      (node (ref "C18") (pin "1") (pinfunction "1_1") (pintype "passive"))
      (node (ref "C19") (pin "2") (pinfunction "2_2") (pintype "passive"))
      (node (ref "C2") (pin "2") (pinfunction "2_2") (pintype "passive"))
      (node (ref "C20") (pin "2") (pinfunction "2_2") (pintype "passive"))
      (node (ref "C22") (pin "2") (pinfunction "2_2") (pintype "passive"))
      (node (ref "C24") (pin "2") (pinfunction "2_2") (pintype "passive"))
      (node (ref "C25") (pin "2") (pinfunction "2_2") (pintype "passive"))
      (node (ref "C26") (pin "2") (pinfunction "2_2") (pintype "passive"))
      (node (ref "C27") (pin "2") (pinfunction "2_2") (pintype "passive"))
      (node (ref "C28") (pin "2") (pinfunction "2_2") (pintype "passive"))
      (node (ref "C29") (pin "2") (pinfunction "2_2") (pintype "passive"))
      (node (ref "C3") (pin "1") (pinfunction "1_1") (pintype "passive"))
      (node (ref "C30") (pin "2") (pinfunction "2_2") (pintype "passive"))
      (node (ref "C31") (pin "1") (pinfunction "1_1") (pintype "passive"))
      (node (ref "C32") (pin "1") (pinfunction "1_1") (pintype "passive"))
      (node (ref "C33") (pin "2") (pinfunction "2_2") (pintype "passive"))
      (node (ref "C34") (pin "2") (pinfunction "2_2") (pintype "passive"))
      (node (ref "C35") (pin "2") (pinfunction "2_2") (pintype "passive"))
      (node (ref "C36") (pin "2") (pinfunction "2_2") (pintype "passive"))
      (node (ref "C38") (pin "2") (pinfunction "2_2") (pintype "passive"))
      (node (ref "C39") (pin "2") (pinfunction "2_2") (pintype "passive"))
      (node (ref "C4") (pin "2") (pinfunction "2_2") (pintype "passive"))
      (node (ref "C40") (pin "2") (pinfunction "2_2") (pintype "passive"))
      (node (ref "C41") (pin "1") (pinfunction "1_1") (pintype "passive"))
      (node (ref "C6") (pin "2") (pinfunction "2_2") (pintype "passive"))
      (node (ref "C7") (pin "2") (pinfunction "2_2") (pintype "passive"))
      (node (ref "C8") (pin "2") (pinfunction "2_2") (pintype "passive"))
      (node (ref "C9") (pin "2") (pinfunction "2_2") (pintype "passive"))
      (node (ref "D5") (pin "1") (pinfunction "A_1") (pintype "passive"))
      (node (ref "IC10") (pin "1") (pinfunction "GND_1") (pintype "bidirectional"))
      (node (ref "IC11") (pin "9") (pinfunction "GND_9") (pintype "power_in"))
      (node (ref "IC12") (pin "9") (pinfunction "GND_9") (pintype "power_in"))
      (node (ref "IC13") (pin "1") (pinfunction "GND_1") (pintype "power_in"))
      (node (ref "IC13") (pin "15") (pinfunction "GND_15") (pintype "power_in"))
      (node (ref "IC13") (pin "38") (pinfunction "GND_38") (pintype "power_in"))
      (node (ref "IC13") (pin "39_1") (pinfunction "GND_39_1") (pintype "power_in"))
      (node (ref "IC13") (pin "39_10") (pinfunction "GND_39_10") (pintype "power_in"))
      (node (ref "IC13") (pin "39_11") (pinfunction "GND_39_11") (pintype "power_in"))
      (node (ref "IC13") (pin "39_12") (pinfunction "GND_39_12") (pintype "power_in"))
      (node (ref "IC13") (pin "39_13") (pinfunction "GND_39_13") (pintype "power_in"))
      (node (ref "IC13") (pin "39_14") (pinfunction "GND_39_14") (pintype "power_in"))
      (node (ref "IC13") (pin "39_15") (pinfunction "GND_39_15") (pintype "power_in"))
      (node (ref "IC13") (pin "39_16") (pinfunction "GND_39_16") (pintype "power_in"))
      (node (ref "IC13") (pin "39_17") (pinfunction "GND_39_17") (pintype "power_in"))
      (node (ref "IC13") (pin "39_18") (pinfunction "GND_39_18") (pintype "power_in"))
      (node (ref "IC13") (pin "39_19") (pinfunction "GND_39_19") (pintype "power_in"))
      (node (ref "IC13") (pin "39_2") (pinfunction "GND_39_2") (pintype "power_in"))
      (node (ref "IC13") (pin "39_20") (pinfunction "GND_39_20") (pintype "power_in"))
      (node (ref "IC13") (pin "39_21") (pinfunction "GND_39_21") (pintype "power_in"))
      (node (ref "IC13") (pin "39_3") (pinfunction "GND_39_3") (pintype "power_in"))
      (node (ref "IC13") (pin "39_4") (pinfunction "GND_39_4") (pintype "power_in"))
      (node (ref "IC13") (pin "39_5") (pinfunction "GND_39_5") (pintype "power_in"))
      (node (ref "IC13") (pin "39_6") (pinfunction "GND_39_6") (pintype "power_in"))
      (node (ref "IC13") (pin "39_7") (pinfunction "GND_39_7") (pintype "power_in"))
      (node (ref "IC13") (pin "39_8") (pinfunction "GND_39_8") (pintype "power_in"))
      (node (ref "IC13") (pin "39_9") (pinfunction "GND_39_9") (pintype "power_in"))
      (node (ref "IC14") (pin "9") (pinfunction "GND_9") (pintype "power_in"))
      (node (ref "IC15") (pin "1") (pinfunction "A1_1") (pintype "input"))
      (node (ref "IC15") (pin "7") (pinfunction "GND_7") (pintype "power_in"))
      (node (ref "IC16") (pin "7") (pinfunction "GND_7") (pintype "power_in"))
      (node (ref "IC3") (pin "1") (pinfunction "A1_1") (pintype "input"))
      (node (ref "IC3") (pin "2") (pinfunction "A0_2") (pintype "input"))
      (node (ref "IC3") (pin "7") (pinfunction "GND_7") (pintype "power_in"))
      (node (ref "IC4") (pin "4") (pinfunction "COM_4") (pintype "power_in"))
      (node (ref "IC5") (pin "3") (pinfunction "S_3") (pintype "passive"))
      (node (ref "IC6") (pin "2") (pinfunction "A0_2") (pintype "input"))
      (node (ref "IC6") (pin "7") (pinfunction "GND_7") (pintype "power_in"))
      (node (ref "IC7") (pin "3") (pinfunction "GND_3") (pintype "power_in"))
      (node (ref "IC7") (pin "5") (pinfunction "~{ON}/OFF_5") (pintype "input"))
      (node (ref "IC7") (pin "6") (pinfunction "TAB_6") (pintype "power_in"))
      (node (ref "IC8") (pin "9") (pinfunction "GND_9") (pintype "power_in"))
      (node (ref "IC9") (pin "1") (pinfunction "ADDR_1") (pintype "input"))
      (node (ref "IC9") (pin "3") (pinfunction "GND_3") (pintype "power_in"))
      (node (ref "J1") (pin "1") (pinfunction "1_1") (pintype "passive"))
      (node (ref "J2") (pin "2") (pinfunction "2_2") (pintype "passive"))
      (node (ref "J3") (pin "2") (pinfunction "2_2") (pintype "passive"))
      (node (ref "J6") (pin "5") (pinfunction "5_5") (pintype "passive"))
      (node (ref "LED1") (pin "2") (pinfunction "2_2") (pintype "passive"))
      (node (ref "R10") (pin "1") (pinfunction "1_1") (pintype "passive"))
      (node (ref "R11") (pin "1") (pinfunction "1_1") (pintype "passive"))
      (node (ref "R14") (pin "2") (pinfunction "2_2") (pintype "passive"))
      (node (ref "R15") (pin "2") (pinfunction "2_2") (pintype "passive"))
      (node (ref "R18") (pin "2") (pinfunction "2_2") (pintype "passive"))
      (node (ref "R2") (pin "1") (pinfunction "1_1") (pintype "passive"))
      (node (ref "R20") (pin "2") (pinfunction "2_2") (pintype "passive"))
      (node (ref "R24") (pin "2") (pinfunction "2_2") (pintype "passive"))
      (node (ref "R25") (pin "2") (pinfunction "2_2") (pintype "passive"))
      (node (ref "R3") (pin "1") (pinfunction "1_1") (pintype "passive"))
      (node (ref "R31") (pin "2") (pinfunction "2_2") (pintype "passive"))
      (node (ref "R8") (pin "2") (pinfunction "2_2") (pintype "passive"))
      (node (ref "USB1") (pin "1") (pinfunction "P1_1") (pintype "passive"))
      (node (ref "USB2") (pin "5") (pinfunction "P5_5") (pintype "passive"))
      (node (ref "USB3") (pin "1") (pinfunction "P1_1") (pintype "passive"))
      (node (ref "USB4") (pin "1") (pinfunction "P1_1") (pintype "passive"))
      (node (ref "USB5") (pin "1") (pinfunction "P1_1") (pintype "passive"))
    )
    (net (code "48") (name "Net-(C13-Pad1)") (class "Default")
      (node (ref "C13") (pin "1") (pinfunction "1_1") (pintype "passive"))
      (node (ref "IC8") (pin "1") (pinfunction "SW_1") (pintype "power_in"))
      (node (ref "IC8") (pin "2") (pinfunction "SW_2") (pintype "power_in"))
      (node (ref "L3") (pin "2") (pinfunction "2_2") (pintype "passive"))
      (node (ref "R22") (pin "1") (pinfunction "1_1") (pintype "passive"))
    )
    (net (code "49") (name "Net-(C18-Pad2)") (class "Default")
      (node (ref "C18") (pin "2") (pinfunction "2_2") (pintype "passive"))
      (node (ref "R22") (pin "2") (pinfunction "2_2") (pintype "passive"))
    )
    (net (code "50") (name "Net-(C21-Pad1)") (class "Default")
      (node (ref "C21") (pin "1") (pinfunction "1_1") (pintype "passive"))
      (node (ref "IC11") (pin "1") (pinfunction "SW_1") (pintype "power_in"))
      (node (ref "IC11") (pin "2") (pinfunction "SW_2") (pintype "power_in"))
      (node (ref "L4") (pin "2") (pinfunction "2_2") (pintype "passive"))
      (node (ref "R27") (pin "1") (pinfunction "1_1") (pintype "passive"))
    )
    (net (code "51") (name "Net-(C23-Pad1)") (class "Default")
      (node (ref "C23") (pin "1") (pinfunction "1_1") (pintype "passive"))
      (node (ref "IC12") (pin "1") (pinfunction "SW_1") (pintype "power_in"))
      (node (ref "IC12") (pin "2") (pinfunction "SW_2") (pintype "power_in"))
      (node (ref "L5") (pin "2") (pinfunction "2_2") (pintype "passive"))
      (node (ref "R28") (pin "1") (pinfunction "1_1") (pintype "passive"))
    )
    (net (code "52") (name "Net-(C31-Pad2)") (class "Default")
      (node (ref "C31") (pin "2") (pinfunction "2_2") (pintype "passive"))
      (node (ref "R27") (pin "2") (pinfunction "2_2") (pintype "passive"))
    )
    (net (code "53") (name "Net-(C32-Pad2)") (class "Default")
      (node (ref "C32") (pin "2") (pinfunction "2_2") (pintype "passive"))
      (node (ref "R28") (pin "2") (pinfunction "2_2") (pintype "passive"))
    )
    (net (code "54") (name "Net-(C37-Pad1)") (class "Default")
      (node (ref "C37") (pin "1") (pinfunction "1_1") (pintype "passive"))
      (node (ref "IC14") (pin "1") (pinfunction "SW_1") (pintype "power_in"))
      (node (ref "IC14") (pin "2") (pinfunction "SW_2") (pintype "power_in"))
      (node (ref "L6") (pin "2") (pinfunction "2_2") (pintype "passive"))
      (node (ref "R35") (pin "1") (pinfunction "1_1") (pintype "passive"))
    )
    (net (code "55") (name "Net-(C41-Pad2)") (class "Default")
      (node (ref "C41") (pin "2") (pinfunction "2_2") (pintype "passive"))
      (node (ref "R35") (pin "2") (pinfunction "2_2") (pintype "passive"))
    )
    (net (code "56") (name "Net-(D1-A)") (class "Default")
      (node (ref "D1") (pin "1") (pinfunction "A_1") (pintype "passive"))
      (node (ref "IC2") (pin "1") (pinfunction "G_1") (pintype "passive"))
      (node (ref "R4") (pin "1") (pinfunction "1_1") (pintype "passive"))
      (node (ref "R7") (pin "1") (pinfunction "1_1") (pintype "passive"))
    )
    (net (code "57") (name "Net-(D1-K)") (class "Default")
      (node (ref "D1") (pin "2") (pinfunction "K_2") (pintype "passive"))
      (node (ref "IC4") (pin "7") (pinfunction "HO_7") (pintype "output"))
      (node (ref "R4") (pin "2") (pinfunction "2_2") (pintype "passive"))
    )
    (net (code "58") (name "Net-(D2-K)") (class "Default")
      (node (ref "C5") (pin "1") (pinfunction "1_1") (pintype "passive"))
      (node (ref "D2") (pin "2") (pinfunction "K_2") (pintype "passive"))
      (node (ref "IC4") (pin "8") (pinfunction "VB_8") (pintype "power_in"))
    )
    (net (code "59") (name "Net-(D3-A)") (class "Default")
      (node (ref "D3") (pin "1") (pinfunction "A_1") (pintype "passive"))
      (node (ref "IC5") (pin "1") (pinfunction "G_1") (pintype "passive"))
      (node (ref "R13") (pin "1") (pinfunction "1_1") (pintype "passive"))
      (node (ref "R14") (pin "1") (pinfunction "1_1") (pintype "passive"))
    )
    (net (code "60") (name "Net-(D3-K)") (class "Default")
      (node (ref "D3") (pin "2") (pinfunction "K_2") (pintype "passive"))
      (node (ref "IC4") (pin "5") (pinfunction "LO_5") (pintype "output"))
      (node (ref "R13") (pin "2") (pinfunction "2_2") (pintype "passive"))
    )
    (net (code "61") (name "Net-(D4-A)") (class "Default")
      (node (ref "D4") (pin "1") (pinfunction "A_1") (pintype "passive"))
      (node (ref "F2") (pin "2") (pinfunction "2_2") (pintype "passive"))
    )
    (net (code "62") (name "Net-(D4-K)") (class "Default")
      (node (ref "C10") (pin "1") (pinfunction "1_1") (pintype "passive"))
      (node (ref "D4") (pin "2") (pinfunction "K_2") (pintype "passive"))
      (node (ref "IC7") (pin "1") (pinfunction "VIN_1") (pintype "power_in"))
    )
    (net (code "63") (name "Net-(D5-K)") (class "Default")
      (node (ref "D5") (pin "2") (pinfunction "K_2") (pintype "passive"))
      (node (ref "IC7") (pin "2") (pinfunction "OUT_2") (pintype "power_in"))
      (node (ref "L2") (pin "1") (pinfunction "1_1") (pintype "passive"))
    )
    (net (code "64") (name "Net-(F1-Pad2)") (class "Default")
      (node (ref "F1") (pin "2") (pinfunction "2_2") (pintype "passive"))
      (node (ref "J3") (pin "1") (pinfunction "1_1") (pintype "passive"))
    )
    (net (code "65") (name "Net-(IC1-S)") (class "Default")
      (node (ref "C2") (pin "1") (pinfunction "1_1") (pintype "passive"))
      (node (ref "IC1") (pin "3") (pinfunction "S_3") (pintype "passive"))
      (node (ref "IC2") (pin "2") (pinfunction "D_2") (pintype "passive"))
      (node (ref "R3") (pin "2") (pinfunction "2_2") (pintype "passive"))
    )
    (net (code "66") (name "Net-(IC2-S)") (class "Default")
      (node (ref "C5") (pin "2") (pinfunction "2_2") (pintype "passive"))
      (node (ref "IC2") (pin "3") (pinfunction "S_3") (pintype "passive"))
      (node (ref "IC4") (pin "6") (pinfunction "VS_6") (pintype "power_in"))
      (node (ref "IC5") (pin "2") (pinfunction "D_2") (pintype "passive"))
      (node (ref "L1") (pin "1") (pinfunction "1_1") (pintype "passive"))
      (node (ref "R7") (pin "2") (pinfunction "2_2") (pintype "passive"))
    )
    (net (code "67") (name "Net-(IC6-IN+)") (class "Default")
      (node (ref "C7") (pin "1") (pinfunction "1_1") (pintype "passive"))
      (node (ref "IC6") (pin "10") (pinfunction "IN+_10") (pintype "input"))
      (node (ref "L1") (pin "2") (pinfunction "2_2") (pintype "passive"))
      (node (ref "R9") (pin "2") (pinfunction "2_2") (pintype "passive"))
    )
    (net (code "68") (name "Net-(IC7-FB)") (class "Default")
      (node (ref "IC7") (pin "4") (pinfunction "FB_4") (pintype "input"))
      (node (ref "R15") (pin "1") (pinfunction "1_1") (pintype "passive"))
      (node (ref "R16") (pin "1") (pinfunction "1_1") (pintype "passive"))
    )
    (net (code "69") (name "Net-(IC8-BST)") (class "Default")
      (node (ref "C13") (pin "2") (pinfunction "2_2") (pintype "passive"))
      (node (ref "IC8") (pin "3") (pinfunction "BST_3") (pintype "passive"))
    )
    (net (code "70") (name "Net-(IC9-VDD)") (class "Default")
      (node (ref "FB1") (pin "1") (pintype "passive"))
      (node (ref "IC9") (pin "8") (pinfunction "VDD_8") (pintype "power_in"))
    )
    (net (code "71") (name "Net-(IC10-V3)") (class "Default")
      (node (ref "C20") (pin "1") (pinfunction "1_1") (pintype "passive"))
      (node (ref "IC10") (pin "4") (pinfunction "V3_4") (pintype "bidirectional"))
    )
    (net (code "72") (name "Net-(IC10-VCC)") (class "Default")
      (node (ref "C19") (pin "1") (pinfunction "1_1") (pintype "passive"))
      (node (ref "IC10") (pin "16") (pinfunction "VCC_16") (pintype "bidirectional"))
      (node (ref "USB2") (pin "1") (pinfunction "P1_1") (pintype "passive"))
    )
    (net (code "73") (name "Net-(IC10-~{DTR})") (class "Default")
      (node (ref "IC10") (pin "13") (pinfunction "~{DTR}_13") (pintype "bidirectional"))
      (node (ref "Q2") (pin "2") (pinfunction "E_2") (pintype "passive"))
      (node (ref "R26") (pin "2") (pinfunction "2_2") (pintype "passive"))
    )
    (net (code "74") (name "Net-(IC10-~{RTS})") (class "Default")
      (node (ref "IC10") (pin "14") (pinfunction "~{RTS}_14") (pintype "bidirectional"))
      (node (ref "Q3") (pin "2") (pinfunction "E_2") (pintype "passive"))
      (node (ref "R23") (pin "2") (pinfunction "2_2") (pintype "passive"))
    )
    (net (code "75") (name "Net-(IC11-BST)") (class "Default")
      (node (ref "C21") (pin "2") (pinfunction "2_2") (pintype "passive"))
      (node (ref "IC11") (pin "3") (pinfunction "BST_3") (pintype "passive"))
    )
    (net (code "76") (name "Net-(IC12-BST)") (class "Default")
      (node (ref "C23") (pin "2") (pinfunction "2_2") (pintype "passive"))
      (node (ref "IC12") (pin "3") (pinfunction "BST_3") (pintype "passive"))
    )
    (net (code "77") (name "Net-(IC14-BST)") (class "Default")
      (node (ref "C37") (pin "2") (pinfunction "2_2") (pintype "passive"))
      (node (ref "IC14") (pin "3") (pinfunction "BST_3") (pintype "passive"))
    )
    (net (code "78") (name "Net-(IC15-IN-)") (class "Default")
      (node (ref "F3") (pin "2") (pinfunction "2_2") (pintype "passive"))
      (node (ref "IC15") (pin "9") (pinfunction "IN-_9") (pintype "input"))
      (node (ref "R36") (pin "2") (pinfunction "2_2") (pintype "passive"))
    )
    (net (code "79") (name "Net-(LED1-Pad1)") (class "Default")
      (node (ref "LED1") (pin "1") (pinfunction "1_1") (pintype "passive"))
      (node (ref "R17") (pin "1") (pinfunction "1_1") (pintype "passive"))
    )
    (net (code "80") (name "Net-(LED2-Pad1)") (class "Default")
      (node (ref "LED2") (pin "1") (pinfunction "1_1") (pintype "passive"))
      (node (ref "R19") (pin "1") (pinfunction "1_1") (pintype "passive"))
    )
    (net (code "81") (name "Net-(Q1-B)") (class "Default")
      (node (ref "Q1") (pin "1") (pinfunction "B_1") (pintype "passive"))
      (node (ref "R12") (pin "1") (pinfunction "1_1") (pintype "passive"))
    )
    (net (code "82") (name "Net-(Q2-B)") (class "Default")
      (node (ref "Q2") (pin "1") (pinfunction "B_1") (pintype "passive"))
      (node (ref "R23") (pin "1") (pinfunction "1_1") (pintype "passive"))
    )
    (net (code "83") (name "Net-(Q3-B)") (class "Default")
      (node (ref "Q3") (pin "1") (pinfunction "B_1") (pintype "passive"))
      (node (ref "R26") (pin "1") (pinfunction "1_1") (pintype "passive"))
    )
    (net (code "84") (name "VBAT") (class "Default")
      (node (ref "F2") (pin "1") (pinfunction "1_1") (pintype "passive"))
      (node (ref "IC15") (pin "10") (pinfunction "IN+_10") (pintype "input"))
      (node (ref "IC16") (pin "10") (pinfunction "IN+_10") (pintype "input"))
      (node (ref "IC6") (pin "8") (pinfunction "VBUS_8") (pintype "power_in"))
      (node (ref "IC6") (pin "9") (pinfunction "IN-_9") (pintype "input"))
      (node (ref "J2") (pin "1") (pinfunction "1_1") (pintype "passive"))
      (node (ref "Q1") (pin "3") (pinfunction "C_3") (pintype "passive"))
      (node (ref "R36") (pin "1") (pinfunction "1_1") (pintype "passive"))
      (node (ref "R37") (pin "1") (pinfunction "1_1") (pintype "passive"))
      (node (ref "R6") (pin "2") (pinfunction "2_2") (pintype "passive"))
      (node (ref "R9") (pin "1") (pinfunction "1_1") (pintype "passive"))
    )
    (net (code "85") (name "VCHARGE") (class "Default")
      (node (ref "C15") (pin "1") (pinfunction "1_1") (pintype "passive"))
      (node (ref "C16") (pin "1") (pinfunction "1_1") (pintype "passive"))
      (node (ref "C26") (pin "1") (pinfunction "1_1") (pintype "passive"))
      (node (ref "C27") (pin "1") (pinfunction "1_1") (pintype "passive"))
      (node (ref "C29") (pin "1") (pinfunction "1_1") (pintype "passive"))
      (node (ref "C30") (pin "1") (pinfunction "1_1") (pintype "passive"))
      (node (ref "C39") (pin "1") (pinfunction "1_1") (pintype "passive"))
      (node (ref "C40") (pin "1") (pinfunction "1_1") (pintype "passive"))
      (node (ref "F3") (pin "1") (pinfunction "1_1") (pintype "passive"))
      (node (ref "IC11") (pin "7") (pinfunction "VIN_7") (pintype "power_in"))
      (node (ref "IC12") (pin "7") (pinfunction "VIN_7") (pintype "power_in"))
      (node (ref "IC14") (pin "7") (pinfunction "VIN_7") (pintype "power_in"))
      (node (ref "IC15") (pin "8") (pinfunction "VBUS_8") (pintype "power_in"))
      (node (ref "IC8") (pin "7") (pinfunction "VIN_7") (pintype "power_in"))
    )
    (net (code "86") (name "VSOL") (class "Default")
      (node (ref "C4") (pin "1") (pinfunction "1_1") (pintype "passive"))
      (node (ref "IC3") (pin "10") (pinfunction "IN+_10") (pintype "input"))
      (node (ref "J1") (pin "2") (pinfunction "2_2") (pintype "passive"))
      (node (ref "R1") (pin "2") (pinfunction "2_2") (pintype "passive"))
      (node (ref "R5") (pin "2") (pinfunction "2_2") (pintype "passive"))
    )
    (net (code "87") (name "VSPEAKER") (class "Default")
      (node (ref "F1") (pin "1") (pinfunction "1_1") (pintype "passive"))
      (node (ref "IC16") (pin "8") (pinfunction "VBUS_8") (pintype "power_in"))
      (node (ref "IC16") (pin "9") (pinfunction "IN-_9") (pintype "input"))
      (node (ref "R37") (pin "2") (pinfunction "2_2") (pintype "passive"))
    )
    (net (code "88") (name "unconnected-(IC3-ALERT-Pad3)") (class "Default")
      (node (ref "IC3") (pin "3") (pinfunction "ALERT_3") (pintype "output+no_connect"))
    )
    (net (code "89") (name "unconnected-(IC6-ALERT-Pad3)") (class "Default")
      (node (ref "IC6") (pin "3") (pinfunction "ALERT_3") (pintype "output+no_connect"))
    )
    (net (code "90") (name "unconnected-(IC8-NC-Pad4)") (class "Default")
      (node (ref "IC8") (pin "4") (pinfunction "NC_4") (pintype "passive+no_connect"))
    )
    (net (code "91") (name "unconnected-(IC10-R232-Pad15)") (class "Default")
      (node (ref "IC10") (pin "15") (pinfunction "R232_15") (pintype "bidirectional+no_connect"))
    )
    (net (code "92") (name "unconnected-(IC10-~{CTS}-Pad9)") (class "Default")
      (node (ref "IC10") (pin "9") (pinfunction "~{CTS}_9") (pintype "bidirectional+no_connect"))
    )
    (net (code "93") (name "unconnected-(IC10-~{DCD}-Pad12)") (class "Default")
      (node (ref "IC10") (pin "12") (pinfunction "~{DCD}_12") (pintype "bidirectional+no_connect"))
    )
    (net (code "94") (name "unconnected-(IC10-~{DSR}-Pad10)") (class "Default")
      (node (ref "IC10") (pin "10") (pinfunction "~{DSR}_10") (pintype "bidirectional+no_connect"))
    )
    (net (code "95") (name "unconnected-(IC10-~{RI}-Pad11)") (class "Default")
      (node (ref "IC10") (pin "11") (pinfunction "~{RI}_11") (pintype "bidirectional+no_connect"))
    )
    (net (code "96") (name "unconnected-(IC11-NC-Pad4)") (class "Default")
      (node (ref "IC11") (pin "4") (pinfunction "NC_4") (pintype "passive+no_connect"))
    )
    (net (code "97") (name "unconnected-(IC12-NC-Pad4)") (class "Default")
      (node (ref "IC12") (pin "4") (pinfunction "NC_4") (pintype "passive+no_connect"))
    )
    (net (code "98") (name "unconnected-(IC13-IO2-Pad24)") (class "Default")
      (node (ref "IC13") (pin "24") (pinfunction "IO2_24") (pintype "bidirectional+no_connect"))
    )
    (net (code "99") (name "unconnected-(IC13-IO13-Pad16)") (class "Default")
      (node (ref "IC13") (pin "16") (pinfunction "IO13_16") (pintype "bidirectional+no_connect"))
    )
    (net (code "100") (name "unconnected-(IC13-IO15-Pad23)") (class "Default")
      (node (ref "IC13") (pin "23") (pinfunction "IO15_23") (pintype "bidirectional+no_connect"))
    )
    (net (code "101") (name "unconnected-(IC13-SCK{slash}CLK-Pad20)") (class "Default")
      (node (ref "IC13") (pin "20") (pinfunction "SCK/CLK_20") (pintype "bidirectional+no_connect"))
    )
    (net (code "102") (name "unconnected-(IC13-SCS{slash}CMD-Pad19)") (class "Default")
      (node (ref "IC13") (pin "19") (pinfunction "SCS/CMD_19") (pintype "bidirectional+no_connect"))
    )
    (net (code "103") (name "unconnected-(IC13-SDI{slash}SD1-Pad22)") (class "Default")
      (node (ref "IC13") (pin "22") (pinfunction "SDI/SD1_22") (pintype "bidirectional+no_connect"))
    )
    (net (code "104") (name "unconnected-(IC13-SDO{slash}SD0-Pad21)") (class "Default")
      (node (ref "IC13") (pin "21") (pinfunction "SDO/SD0_21") (pintype "bidirectional+no_connect"))
    )
    (net (code "105") (name "unconnected-(IC13-SHD{slash}SD2-Pad17)") (class "Default")
      (node (ref "IC13") (pin "17") (pinfunction "SHD/SD2_17") (pintype "bidirectional+no_connect"))
    )
    (net (code "106") (name "unconnected-(IC13-SWP{slash}SD3-Pad18)") (class "Default")
      (node (ref "IC13") (pin "18") (pinfunction "SWP/SD3_18") (pintype "bidirectional+no_connect"))
    )
    (net (code "107") (name "unconnected-(IC14-NC-Pad4)") (class "Default")
      (node (ref "IC14") (pin "4") (pinfunction "NC_4") (pintype "passive+no_connect"))
    )
    (net (code "108") (name "unconnected-(IC15-ALERT-Pad3)") (class "Default")
      (node (ref "IC15") (pin "3") (pinfunction "ALERT_3") (pintype "output+no_connect"))
    )
    (net (code "109") (name "unconnected-(IC16-ALERT-Pad3)") (class "Default")
      (node (ref "IC16") (pin "3") (pinfunction "ALERT_3") (pintype "output+no_connect"))
    )
    (net (code "110") (name "unconnected-(USB1-P4-Pad4)") (class "Default")
      (node (ref "USB1") (pin "4") (pinfunction "P4_4") (pintype "passive+no_connect"))
    )
    (net (code "111") (name "unconnected-(USB2-P4-Pad4)") (class "Default")
      (node (ref "USB2") (pin "4") (pinfunction "P4_4") (pintype "passive"))
    )
    (net (code "112") (name "unconnected-(USB3-P4-Pad4)") (class "Default")
      (node (ref "USB3") (pin "4") (pinfunction "P4_4") (pintype "passive+no_connect"))
    )
    (net (code "113") (name "unconnected-(USB4-P4-Pad4)") (class "Default")
      (node (ref "USB4") (pin "4") (pinfunction "P4_4") (pintype "passive+no_connect"))
    )
    (net (code "114") (name "unconnected-(USB5-P4-Pad4)") (class "Default")
      (node (ref "USB5") (pin "4") (pinfunction "P4_4") (pintype "passive+no_connect"))
    )
  )
)
